# Arduino.net
KiCad netlist of a schematic drawn in Altium Designer
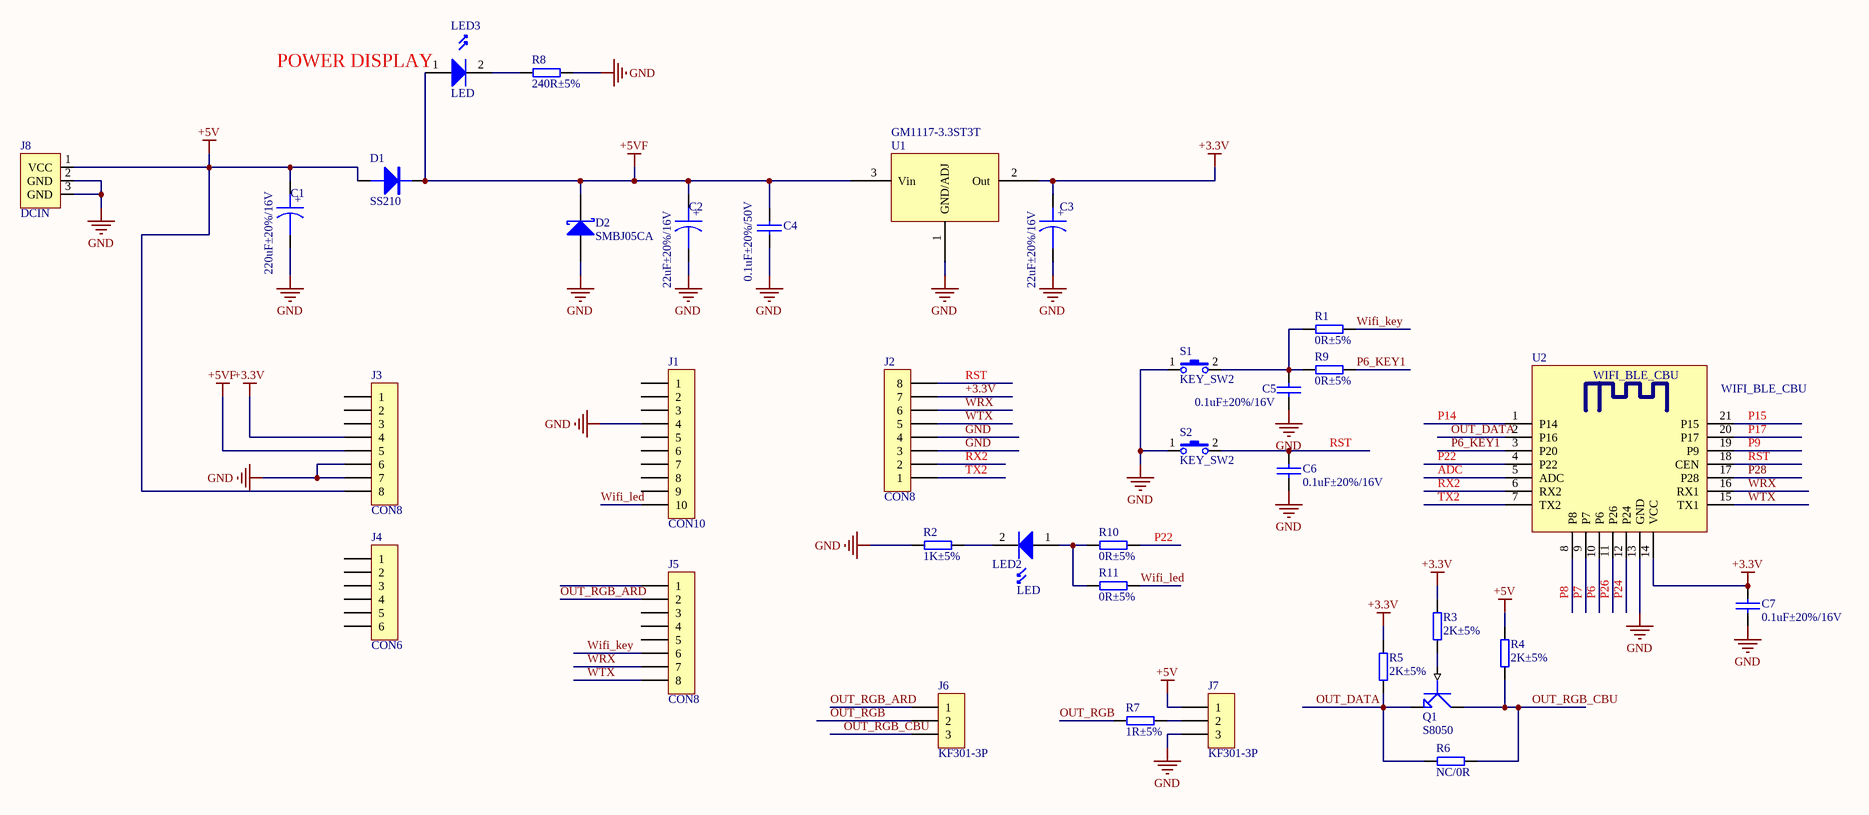
[diagram p0: Arduino幻彩灯带.SchDoc]

(export (version "E")
  (design (tool "Eeschema 10.0.6"))
  (components
    (comp (ref "C1")
      (value "220uF±20%/16V")
      (footprint "CD0.15")
      (description "Capacitor")
      (libsource (lib "*") (part "CAPACITOR POL"))
    )
    (comp (ref "C2")
      (value "22uF±20%/16V")
      (footprint "钽电容B3528")
      (description "Capacitor")
      (libsource (lib "*") (part "CAPACITOR POL"))
    )
    (comp (ref "C3")
      (value "22uF±20%/16V")
      (footprint "钽电容B3528")
      (description "Capacitor")
      (libsource (lib "*") (part "CAPACITOR POL"))
    )
    (comp (ref "C4")
      (value "0.1uF±20%/50V")
      (footprint "C0603")
      (description "Capacitor")
      (libsource (lib "昊华元件库sch") (part "CAP"))
    )
    (comp (ref "C5")
      (value "0.1uF±20%/16V")
      (footprint "C0603")
      (description "Capacitor")
      (libsource (lib "昊华元件库sch") (part "CAP"))
    )
    (comp (ref "C6")
      (value "0.1uF±20%/16V")
      (footprint "C0603")
      (description "Capacitor")
      (libsource (lib "昊华元件库sch") (part "CAP"))
    )
    (comp (ref "C7")
      (value "0.1uF±20%/16V")
      (footprint "C0603")
      (description "Capacitor")
      (libsource (lib "昊华元件库sch") (part "CAP"))
    )
    (comp (ref "D1")
      (value "SS210")
      (footprint "SMA(DO-214AC)")
      (description "Diode")
      (libsource (lib "小马元件库sch") (part "Diode1"))
    )
    (comp (ref "D2")
      (value "SMBJ05CA")
      (footprint "SMB(DO-214AA)")
      (description "Schottky Diode")
      (fields (field (name "MFR") "Toshiba"))
      (libsource (lib "Miscellaneous Devices") (part "D Schottky"))
    )
    (comp (ref "J1")
      (value "CON10")
      (footprint "HDR1X10Z")
      (description "Connector")
      (libsource (lib "小马元件库sch") (part "CON10"))
    )
    (comp (ref "J2")
      (value "CON8")
      (footprint "HDR1X8Z")
      (description "Connector")
      (libsource (lib "小马元件库sch") (part "CON8"))
    )
    (comp (ref "J3")
      (value "CON8")
      (footprint "HDR1X8Z")
      (description "Connector")
      (libsource (lib "") (part "CON8_1"))
    )
    (comp (ref "J4")
      (value "CON6")
      (footprint "HDR1X6Z")
      (description "Connector")
      (libsource (lib "小马元件库sch") (part "CON6"))
    )
    (comp (ref "J5")
      (value "CON8")
      (footprint "HDR1X8Z")
      (description "Connector")
      (libsource (lib "") (part "CON8_1"))
    )
    (comp (ref "J6")
      (value "KF301-3P")
      (footprint "SIP3 - 2.54")
      (description "Connector")
      (libsource (lib "小马元件库sch") (part "CON3"))
    )
    (comp (ref "J7")
      (value "KF301-3P")
      (footprint "SIP3 - 2.54")
      (description "Connector")
      (libsource (lib "小马元件库sch") (part "CON3"))
    )
    (comp (ref "J8")
      (value "DCIN")
      (footprint "DC-IN-TH_DC-044-20A")
      (libsource (lib "altium-import") (part "root_0_DC_"))
    )
    (comp (ref "LED2")
      (value "LED")
      (footprint "LED0805_1")
      (fields (field (name "PUBLISHER") "*"))
      (libsource (lib "小马元件库sch") (part "LED"))
    )
    (comp (ref "LED3")
      (value "LED")
      (footprint "LED0805_1")
      (fields (field (name "PUBLISHER") "*"))
      (libsource (lib "小马元件库sch") (part "LED"))
    )
    (comp (ref "Q1")
      (value "S8050")
      (footprint "SOT-23-NPN")
      (description "NPN Transistor")
      (libsource (lib "小马元件库sch") (part "NPN"))
    )
    (comp (ref "R1") (value "0R±5%") (footprint "R0603") (libsource (lib "昊华元件库sch") (part "RES5")))
    (comp (ref "R2") (value "1K±5%") (footprint "R0603") (libsource (lib "昊华元件库sch") (part "RES5")))
    (comp (ref "R3") (value "2K±5%") (footprint "R0603") (libsource (lib "昊华元件库sch") (part "RES5")))
    (comp (ref "R4") (value "2K±5%") (footprint "R0603") (libsource (lib "昊华元件库sch") (part "RES5")))
    (comp (ref "R5") (value "2K±5%") (footprint "R0603") (libsource (lib "昊华元件库sch") (part "RES5")))
    (comp (ref "R6") (value "NC/0R") (footprint "R0603") (libsource (lib "昊华元件库sch") (part "RES5")))
    (comp (ref "R7") (value "1R±5%") (footprint "R0603") (libsource (lib "昊华元件库sch") (part "RES5")))
    (comp (ref "R8") (value "240R±5%") (footprint "R0603") (libsource (lib "昊华元件库sch") (part "RES5")))
    (comp (ref "R9") (value "0R±5%") (footprint "R0603") (libsource (lib "昊华元件库sch") (part "RES5")))
    (comp (ref "R10") (value "0R±5%") (footprint "R0603") (libsource (lib "昊华元件库sch") (part "RES5")))
    (comp (ref "R11") (value "0R±5%") (footprint "R0603") (libsource (lib "昊华元件库sch") (part "RES5")))
    (comp (ref "S1") (value "KEY_SW2") (footprint "3*6*2.5-SM") (libsource (lib "小马元件库sch") (part "KEY_SW2")))
    (comp (ref "S2") (value "KEY_SW2") (footprint "3*6*2.5-SM") (libsource (lib "小马元件库sch") (part "KEY_SW2")))
    (comp (ref "U1") (value "GM1117-3.3ST3T") (footprint "SOT-223") (libsource (lib "mylib") (part "GM1117")))
    (comp (ref "U2")
      (value "WIFI_BLE_CBU")
      (footprint "WIFI_BLE_CBU")
      (description "Module")
      (libsource (lib "TYModeSchlib V03") (part "WIFI_BLE_CBU"))
    )
  )
  (nets
    (net (code "1") (name "+3.3V") (class "Default")
      (node (ref "C3") (pin "1") (pinfunction "1_1") (pintype "passive"))
      (node (ref "C7") (pin "2") (pinfunction "2_2") (pintype "passive"))
      (node (ref "J2") (pin "7") (pinfunction "7_7") (pintype "passive"))
      (node (ref "J3") (pin "4") (pinfunction "4_4") (pintype "passive"))
      (node (ref "R3") (pin "1") (pinfunction "1_1") (pintype "passive"))
      (node (ref "R5") (pin "1") (pinfunction "1_1") (pintype "passive"))
      (node (ref "U1") (pin "2") (pinfunction "Out_2") (pintype "passive"))
      (node (ref "U2") (pin "14") (pinfunction "VCC_14") (pintype "passive"))
    )
    (net (code "2") (name "+5V") (class "Default")
      (node (ref "C1") (pin "1") (pinfunction "1_1") (pintype "passive"))
      (node (ref "D1") (pin "1") (pinfunction "1_1") (pintype "passive"))
      (node (ref "J3") (pin "8") (pinfunction "8_8") (pintype "passive"))
      (node (ref "J7") (pin "1") (pinfunction "1_1") (pintype "passive"))
      (node (ref "J8") (pin "1") (pinfunction "VCC_1") (pintype "passive"))
      (node (ref "R4") (pin "1") (pinfunction "1_1") (pintype "passive"))
    )
    (net (code "3") (name "+5VF") (class "Default")
      (node (ref "C2") (pin "1") (pinfunction "1_1") (pintype "passive"))
      (node (ref "C4") (pin "1") (pinfunction "1_1") (pintype "passive"))
      (node (ref "D1") (pin "2") (pinfunction "2_2") (pintype "passive"))
      (node (ref "D2") (pin "2") (pinfunction "K_2") (pintype "passive"))
      (node (ref "J3") (pin "5") (pinfunction "5_5") (pintype "passive"))
      (node (ref "LED3") (pin "1") (pinfunction "1_1") (pintype "passive"))
      (node (ref "U1") (pin "3") (pinfunction "Vin_3") (pintype "passive"))
    )
    (net (code "4") (name "/ADC") (class "Default")
      (node (ref "U2") (pin "5") (pinfunction "ADC_5") (pintype "passive"))
    )
    (net (code "5") (name "/OUT_DATA") (class "Default")
      (node (ref "Q1") (pin "1") (pinfunction "E_1") (pintype "passive"))
      (node (ref "R5") (pin "2") (pinfunction "2_2") (pintype "passive"))
      (node (ref "R6") (pin "1") (pinfunction "1_1") (pintype "passive"))
      (node (ref "U2") (pin "2") (pinfunction "P16_2") (pintype "passive"))
    )
    (net (code "6") (name "/OUT_RGB") (class "Default")
      (node (ref "J6") (pin "2") (pinfunction "2_2") (pintype "passive"))
      (node (ref "R7") (pin "1") (pinfunction "1_1") (pintype "passive"))
    )
    (net (code "7") (name "/OUT_RGB_ARD") (class "Default")
      (node (ref "J5") (pin "2") (pinfunction "2_2") (pintype "passive"))
      (node (ref "J6") (pin "1") (pinfunction "1_1") (pintype "passive"))
    )
    (net (code "8") (name "/OUT_RGB_CBU") (class "Default")
      (node (ref "J6") (pin "3") (pinfunction "3_3") (pintype "passive"))
      (node (ref "Q1") (pin "3") (pinfunction "C_3") (pintype "passive"))
      (node (ref "R4") (pin "2") (pinfunction "2_2") (pintype "passive"))
      (node (ref "R6") (pin "2") (pinfunction "2_2") (pintype "passive"))
    )
    (net (code "9") (name "/P6") (class "Default")
      (node (ref "U2") (pin "10") (pinfunction "P6_10") (pintype "passive"))
    )
    (net (code "10") (name "/P6_KEY1") (class "Default")
      (node (ref "R9") (pin "1") (pinfunction "1_1") (pintype "passive"))
      (node (ref "U2") (pin "3") (pinfunction "P20_3") (pintype "passive"))
    )
    (net (code "11") (name "/P7") (class "Default")
      (node (ref "U2") (pin "9") (pinfunction "P7_9") (pintype "passive"))
    )
    (net (code "12") (name "/P8") (class "Default")
      (node (ref "U2") (pin "8") (pinfunction "P8_8") (pintype "passive"))
    )
    (net (code "13") (name "/P9") (class "Default")
      (node (ref "U2") (pin "19") (pinfunction "P9_19") (pintype "passive"))
    )
    (net (code "14") (name "/P14") (class "Default")
      (node (ref "U2") (pin "1") (pinfunction "P14_1") (pintype "passive"))
    )
    (net (code "15") (name "/P15") (class "Default")
      (node (ref "U2") (pin "21") (pinfunction "P15_21") (pintype "passive"))
    )
    (net (code "16") (name "/P17") (class "Default")
      (node (ref "U2") (pin "20") (pinfunction "P17_20") (pintype "passive"))
    )
    (net (code "17") (name "/P22") (class "Default")
      (node (ref "R10") (pin "1") (pinfunction "1_1") (pintype "passive"))
      (node (ref "U2") (pin "4") (pinfunction "P22_4") (pintype "passive"))
    )
    (net (code "18") (name "/P24") (class "Default")
      (node (ref "U2") (pin "12") (pinfunction "P24_12") (pintype "passive"))
    )
    (net (code "19") (name "/P26") (class "Default")
      (node (ref "U2") (pin "11") (pinfunction "P26_11") (pintype "passive"))
    )
    (net (code "20") (name "/P28") (class "Default")
      (node (ref "U2") (pin "17") (pinfunction "P28_17") (pintype "passive"))
    )
    (net (code "21") (name "/RST") (class "Default")
      (node (ref "C6") (pin "1") (pinfunction "1_1") (pintype "passive"))
      (node (ref "J2") (pin "8") (pinfunction "8_8") (pintype "passive"))
      (node (ref "S2") (pin "2") (pinfunction "2_2") (pintype "passive"))
      (node (ref "U2") (pin "18") (pinfunction "CEN_18") (pintype "passive"))
    )
    (net (code "22") (name "/RX2") (class "Default")
      (node (ref "J2") (pin "2") (pinfunction "2_2") (pintype "passive"))
      (node (ref "U2") (pin "6") (pinfunction "RX2_6") (pintype "passive"))
    )
    (net (code "23") (name "/TX2") (class "Default")
      (node (ref "J2") (pin "1") (pinfunction "1_1") (pintype "passive"))
      (node (ref "U2") (pin "7") (pinfunction "TX2_7") (pintype "passive"))
    )
    (net (code "24") (name "/WRX") (class "Default")
      (node (ref "J2") (pin "6") (pinfunction "6_6") (pintype "passive"))
      (node (ref "J5") (pin "7") (pinfunction "7_7") (pintype "passive"))
      (node (ref "U2") (pin "16") (pinfunction "RX1_16") (pintype "passive"))
    )
    (net (code "25") (name "/WTX") (class "Default")
      (node (ref "J2") (pin "5") (pinfunction "5_5") (pintype "passive"))
      (node (ref "J5") (pin "8") (pinfunction "8_8") (pintype "passive"))
      (node (ref "U2") (pin "15") (pinfunction "TX1_15") (pintype "passive"))
    )
    (net (code "26") (name "/Wifi_key") (class "Default")
      (node (ref "J5") (pin "6") (pinfunction "6_6") (pintype "passive"))
      (node (ref "R1") (pin "1") (pinfunction "1_1") (pintype "passive"))
    )
    (net (code "27") (name "/Wifi_led") (class "Default")
      (node (ref "J1") (pin "10") (pinfunction "10_10") (pintype "passive"))
      (node (ref "R11") (pin "1") (pinfunction "1_1") (pintype "passive"))
    )
    (net (code "28") (name "GND") (class "Default")
      (node (ref "C1") (pin "2") (pinfunction "2_2") (pintype "passive"))
      (node (ref "C2") (pin "2") (pinfunction "2_2") (pintype "passive"))
      (node (ref "C3") (pin "2") (pinfunction "2_2") (pintype "passive"))
      (node (ref "C4") (pin "2") (pinfunction "2_2") (pintype "passive"))
      (node (ref "C5") (pin "1") (pinfunction "1_1") (pintype "passive"))
      (node (ref "C6") (pin "2") (pinfunction "2_2") (pintype "passive"))
      (node (ref "C7") (pin "1") (pinfunction "1_1") (pintype "passive"))
      (node (ref "D2") (pin "1") (pinfunction "A_1") (pintype "passive"))
      (node (ref "J1") (pin "4") (pinfunction "4_4") (pintype "passive"))
      (node (ref "J2") (pin "3") (pinfunction "3_3") (pintype "passive"))
      (node (ref "J2") (pin "4") (pinfunction "4_4") (pintype "passive"))
      (node (ref "J3") (pin "6") (pinfunction "6_6") (pintype "passive"))
      (node (ref "J3") (pin "7") (pinfunction "7_7") (pintype "passive"))
      (node (ref "J7") (pin "3") (pinfunction "3_3") (pintype "passive"))
      (node (ref "J8") (pin "2") (pinfunction "GND_2") (pintype "passive"))
      (node (ref "J8") (pin "3") (pinfunction "GND_3") (pintype "passive"))
      (node (ref "R2") (pin "2") (pinfunction "2_2") (pintype "passive"))
      (node (ref "R8") (pin "2") (pinfunction "2_2") (pintype "passive"))
      (node (ref "S1") (pin "1") (pinfunction "1_1") (pintype "passive"))
      (node (ref "S2") (pin "1") (pinfunction "1_1") (pintype "passive"))
      (node (ref "U1") (pin "1") (pinfunction "GND/ADJ_1") (pintype "passive"))
      (node (ref "U2") (pin "13") (pinfunction "GND_13") (pintype "passive"))
    )
    (net (code "29") (name "Net-(C5-Pad2)") (class "Default")
      (node (ref "C5") (pin "2") (pinfunction "2_2") (pintype "passive"))
      (node (ref "R1") (pin "2") (pinfunction "2_2") (pintype "passive"))
      (node (ref "R9") (pin "2") (pinfunction "2_2") (pintype "passive"))
      (node (ref "S1") (pin "2") (pinfunction "2_2") (pintype "passive"))
    )
    (net (code "30") (name "Net-(J7-Pad2)") (class "Default")
      (node (ref "J7") (pin "2") (pinfunction "2_2") (pintype "passive"))
      (node (ref "R7") (pin "2") (pinfunction "2_2") (pintype "passive"))
    )
    (net (code "31") (name "Net-(LED2-Pad1)") (class "Default")
      (node (ref "LED2") (pin "1") (pinfunction "1_1") (pintype "passive"))
      (node (ref "R10") (pin "2") (pinfunction "2_2") (pintype "passive"))
      (node (ref "R11") (pin "2") (pinfunction "2_2") (pintype "passive"))
    )
    (net (code "32") (name "Net-(LED2-Pad2)") (class "Default")
      (node (ref "LED2") (pin "2") (pinfunction "2_2") (pintype "passive"))
      (node (ref "R2") (pin "1") (pinfunction "1_1") (pintype "passive"))
    )
    (net (code "33") (name "Net-(LED3-Pad2)") (class "Default")
      (node (ref "LED3") (pin "2") (pinfunction "2_2") (pintype "passive"))
      (node (ref "R8") (pin "1") (pinfunction "1_1") (pintype "passive"))
    )
    (net (code "34") (name "Net-(Q1-B)") (class "Default")
      (node (ref "Q1") (pin "2") (pinfunction "B_2") (pintype "input"))
      (node (ref "R3") (pin "2") (pinfunction "2_2") (pintype "passive"))
    )
    (net (code "35") (name "unconnected-(J1-Pad1)") (class "Default")
      (node (ref "J1") (pin "1") (pinfunction "1_1") (pintype "passive"))
    )
    (net (code "36") (name "unconnected-(J1-Pad2)") (class "Default")
      (node (ref "J1") (pin "2") (pinfunction "2_2") (pintype "passive"))
    )
    (net (code "37") (name "unconnected-(J1-Pad3)") (class "Default")
      (node (ref "J1") (pin "3") (pinfunction "3_3") (pintype "passive"))
    )
    (net (code "38") (name "unconnected-(J1-Pad5)") (class "Default")
      (node (ref "J1") (pin "5") (pinfunction "5_5") (pintype "passive"))
    )
    (net (code "39") (name "unconnected-(J1-Pad6)") (class "Default")
      (node (ref "J1") (pin "6") (pinfunction "6_6") (pintype "passive"))
    )
    (net (code "40") (name "unconnected-(J1-Pad7)") (class "Default")
      (node (ref "J1") (pin "7") (pinfunction "7_7") (pintype "passive"))
    )
    (net (code "41") (name "unconnected-(J1-Pad8)") (class "Default")
      (node (ref "J1") (pin "8") (pinfunction "8_8") (pintype "passive"))
    )
    (net (code "42") (name "unconnected-(J1-Pad9)") (class "Default")
      (node (ref "J1") (pin "9") (pinfunction "9_9") (pintype "passive"))
    )
    (net (code "43") (name "unconnected-(J3-Pad1)") (class "Default")
      (node (ref "J3") (pin "1") (pinfunction "1_1") (pintype "passive"))
    )
    (net (code "44") (name "unconnected-(J3-Pad2)") (class "Default")
      (node (ref "J3") (pin "2") (pinfunction "2_2") (pintype "passive"))
    )
    (net (code "45") (name "unconnected-(J3-Pad3)") (class "Default")
      (node (ref "J3") (pin "3") (pinfunction "3_3") (pintype "passive"))
    )
    (net (code "46") (name "unconnected-(J4-Pad1)") (class "Default")
      (node (ref "J4") (pin "1") (pinfunction "1_1") (pintype "passive"))
    )
    (net (code "47") (name "unconnected-(J4-Pad2)") (class "Default")
      (node (ref "J4") (pin "2") (pinfunction "2_2") (pintype "passive"))
    )
    (net (code "48") (name "unconnected-(J4-Pad3)") (class "Default")
      (node (ref "J4") (pin "3") (pinfunction "3_3") (pintype "passive"))
    )
    (net (code "49") (name "unconnected-(J4-Pad4)") (class "Default")
      (node (ref "J4") (pin "4") (pinfunction "4_4") (pintype "passive"))
    )
    (net (code "50") (name "unconnected-(J4-Pad5)") (class "Default")
      (node (ref "J4") (pin "5") (pinfunction "5_5") (pintype "passive"))
    )
    (net (code "51") (name "unconnected-(J4-Pad6)") (class "Default")
      (node (ref "J4") (pin "6") (pinfunction "6_6") (pintype "passive"))
    )
    (net (code "52") (name "unconnected-(J5-Pad1)") (class "Default")
      (node (ref "J5") (pin "1") (pinfunction "1_1") (pintype "passive"))
    )
    (net (code "53") (name "unconnected-(J5-Pad3)") (class "Default")
      (node (ref "J5") (pin "3") (pinfunction "3_3") (pintype "passive"))
    )
    (net (code "54") (name "unconnected-(J5-Pad4)") (class "Default")
      (node (ref "J5") (pin "4") (pinfunction "4_4") (pintype "passive"))
    )
    (net (code "55") (name "unconnected-(J5-Pad5)") (class "Default")
      (node (ref "J5") (pin "5") (pinfunction "5_5") (pintype "passive"))
    )
  )
)
